# boomerang.net
KiCad netlist of a schematic drawn in EAGLE
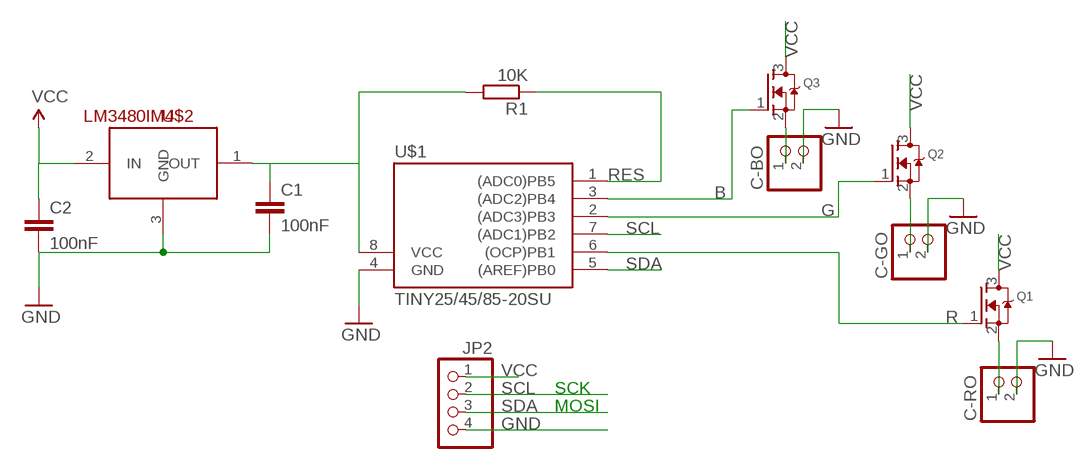
[diagram p0: schematic, sheet 1]

(export (version "E")
  (design (tool "Eeschema 10.0.6"))
  (components
    (comp (ref "C-BO")
      (value "PINHD-1X2M")
      (footprint "eagle-import:1X02M")
      (libsource (lib "eagle-import") (part "PINHD-1X2M"))
    )
    (comp (ref "C-GO")
      (value "PINHD-1X2M")
      (footprint "eagle-import:1X02M")
      (libsource (lib "eagle-import") (part "PINHD-1X2M"))
    )
    (comp (ref "C-RO")
      (value "PINHD-1X2M")
      (footprint "eagle-import:1X02M")
      (libsource (lib "eagle-import") (part "PINHD-1X2M"))
    )
    (comp (ref "C1")
      (value "100nF")
      (footprint "eagle-import:C0603")
      (libsource (lib "eagle-import") (part "C-EUC0603"))
    )
    (comp (ref "C2")
      (value "100nF")
      (footprint "eagle-import:C0603")
      (libsource (lib "eagle-import") (part "C-EUC0603"))
    )
    (comp (ref "JP2")
      (value "PINHD-1X4_2.54-SMD-90°")
      (footprint "eagle-import:1X04SMD_90")
      (libsource (lib "eagle-import") (part "PINHD-1X4_2.54-SMD-90°"))
    )
    (comp (ref "Q1")
      (value "MOSFET-NREFLOW")
      (footprint "eagle-import:SOT23")
      (libsource (lib "eagle-import") (part "MOSFET-NREFLOW"))
    )
    (comp (ref "Q2")
      (value "MOSFET-NREFLOW")
      (footprint "eagle-import:SOT23")
      (libsource (lib "eagle-import") (part "MOSFET-NREFLOW"))
    )
    (comp (ref "Q3")
      (value "MOSFET-NREFLOW")
      (footprint "eagle-import:SOT23")
      (libsource (lib "eagle-import") (part "MOSFET-NREFLOW"))
    )
    (comp (ref "R1")
      (value "10K")
      (footprint "eagle-import:R0603")
      (libsource (lib "eagle-import") (part "R-EU_R0603"))
    )
    (comp (ref "U$1")
      (value "TINY25/45/85-20SU")
      (footprint "eagle-import:SOIC8")
      (libsource (lib "eagle-import") (part "TINY25/45/85-20SU"))
    )
    (comp (ref "U$2")
      (value "LM3480IM4")
      (footprint "eagle-import:SOT23-3")
      (libsource (lib "eagle-import") (part "LM3480IM4"))
    )
  )
  (nets
    (net (code "1") (name "/B") (class "Default")
      (node (ref "Q3") (pin "1") (pinfunction "G_1") (pintype "bidirectional"))
      (node (ref "U$1") (pin "3") (pinfunction "(ADC2)PB4_3") (pintype "bidirectional"))
    )
    (net (code "2") (name "/G") (class "Default")
      (node (ref "Q2") (pin "1") (pinfunction "G_1") (pintype "bidirectional"))
      (node (ref "U$1") (pin "2") (pinfunction "(ADC3)PB3_2") (pintype "bidirectional"))
    )
    (net (code "3") (name "/R") (class "Default")
      (node (ref "Q1") (pin "1") (pinfunction "G_1") (pintype "bidirectional"))
      (node (ref "U$1") (pin "6") (pinfunction "(OCP)PB1_6") (pintype "bidirectional"))
    )
    (net (code "4") (name "/RES") (class "Default")
      (node (ref "R1") (pin "1") (pinfunction "1_1") (pintype "passive"))
      (node (ref "U$1") (pin "1") (pinfunction "(ADC0)PB5_1") (pintype "bidirectional"))
    )
    (net (code "5") (name "/SCL") (class "Default")
      (node (ref "JP2") (pin "2") (pinfunction "2_2") (pintype "passive"))
      (node (ref "U$1") (pin "7") (pinfunction "(ADC1)PB2_7") (pintype "bidirectional"))
    )
    (net (code "6") (name "/SDA") (class "Default")
      (node (ref "JP2") (pin "3") (pinfunction "3_3") (pintype "passive"))
      (node (ref "U$1") (pin "5") (pinfunction "(AREF)PB0_5") (pintype "bidirectional"))
    )
    (net (code "7") (name "GND") (class "Default")
      (node (ref "C-BO") (pin "2") (pinfunction "2_2") (pintype "passive"))
      (node (ref "C-GO") (pin "2") (pinfunction "2_2") (pintype "passive"))
      (node (ref "C-RO") (pin "2") (pinfunction "2_2") (pintype "passive"))
      (node (ref "C1") (pin "2") (pinfunction "2_2") (pintype "passive"))
      (node (ref "C2") (pin "2") (pinfunction "2_2") (pintype "passive"))
      (node (ref "JP2") (pin "4") (pinfunction "4_4") (pintype "passive"))
      (node (ref "U$1") (pin "4") (pinfunction "GND_4") (pintype "power_in"))
      (node (ref "U$2") (pin "3") (pinfunction "GND_3") (pintype "bidirectional"))
    )
    (net (code "8") (name "Net-(Q1-S)") (class "Default")
      (node (ref "C-RO") (pin "1") (pinfunction "1_1") (pintype "passive"))
      (node (ref "Q1") (pin "2") (pinfunction "S_2") (pintype "bidirectional"))
    )
    (net (code "9") (name "Net-(Q2-S)") (class "Default")
      (node (ref "C-GO") (pin "1") (pinfunction "1_1") (pintype "passive"))
      (node (ref "Q2") (pin "2") (pinfunction "S_2") (pintype "bidirectional"))
    )
    (net (code "10") (name "Net-(Q3-S)") (class "Default")
      (node (ref "C-BO") (pin "1") (pinfunction "1_1") (pintype "passive"))
      (node (ref "Q3") (pin "2") (pinfunction "S_2") (pintype "bidirectional"))
    )
    (net (code "11") (name "Net-(U$1-VCC)") (class "Default")
      (node (ref "C1") (pin "1") (pinfunction "1_1") (pintype "passive"))
      (node (ref "R1") (pin "2") (pinfunction "2_2") (pintype "passive"))
      (node (ref "U$1") (pin "8") (pinfunction "VCC_8") (pintype "power_in"))
      (node (ref "U$2") (pin "1") (pinfunction "OUT_1") (pintype "bidirectional"))
    )
    (net (code "12") (name "VCC") (class "Default")
      (node (ref "C2") (pin "1") (pinfunction "1_1") (pintype "passive"))
      (node (ref "JP2") (pin "1") (pinfunction "1_1") (pintype "passive"))
      (node (ref "Q1") (pin "3") (pinfunction "D_3") (pintype "bidirectional"))
      (node (ref "Q2") (pin "3") (pinfunction "D_3") (pintype "bidirectional"))
      (node (ref "Q3") (pin "3") (pinfunction "D_3") (pintype "bidirectional"))
      (node (ref "U$2") (pin "2") (pinfunction "IN_2") (pintype "bidirectional"))
    )
  )
)
